# config-bank6.net
KiCad netlist of a schematic drawn in Altium Designer
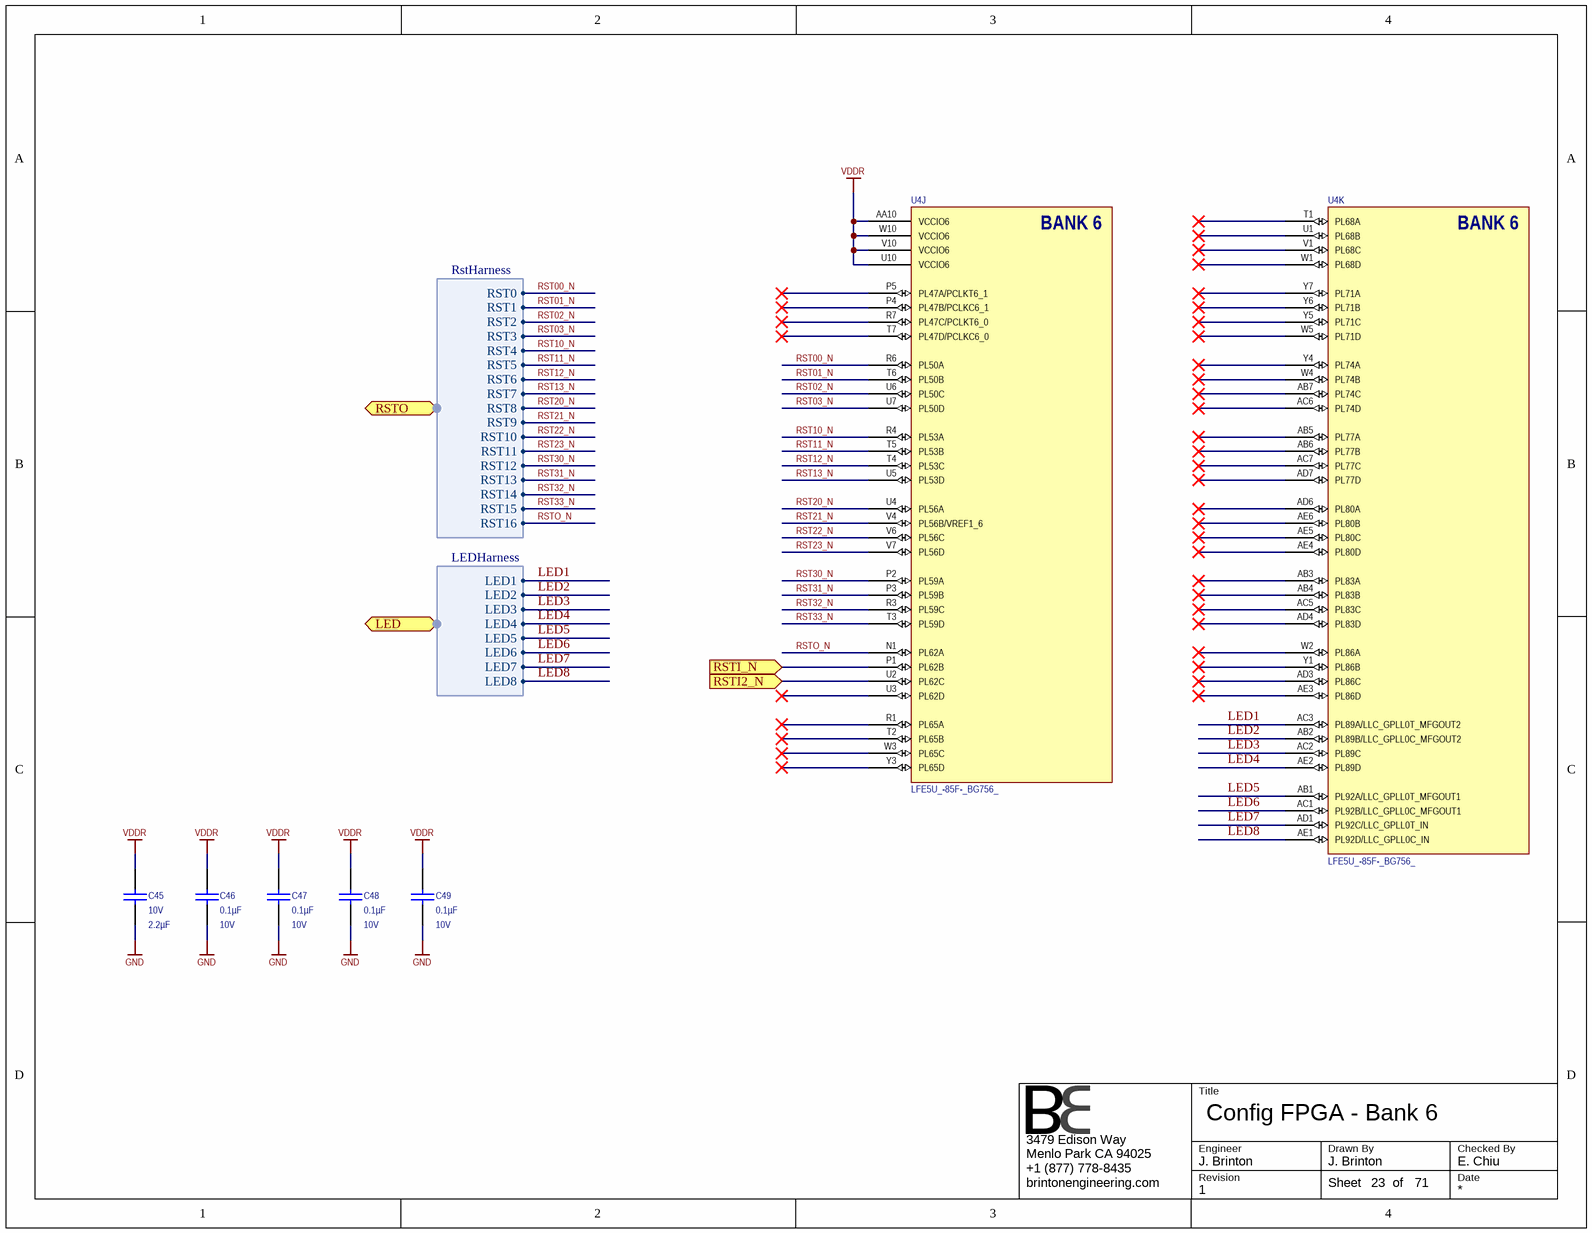
[diagram p0: config-bank6.SchDoc]

(export (version "E")
  (design (tool "Eeschema 10.0.6"))
  (components
    (comp (ref "C45")
      (value "GRM188R71A225KE15D")
      (footprint "CAPC1608X90N")
      (description "CAP CER 2.2UF 10V 10% X7R 0603")
      (fields
        (field (name "MANUFACTURER") "Murata Electronics North America")
        (field (name "TOLERANCE") "±10%")
        (field (name "VOLTAGE - RATED") "10V")
        (field (name "CAPACITANCE") "2.2µF")
      )
      (libsource (lib "murata") (part "GRM188R71A225KE15D"))
    )
    (comp (ref "C46")
      (value "GRM155R71A104KA01J")
      (footprint "CAPC1005X56N")
      (description "CAP CER 0.1UF 10V 10% X7R 0402")
      (fields
        (field (name "MANUFACTURER") "Murata Electronics North America")
        (field (name "TOLERANCE") "±10%")
        (field (name "CAPACITANCE") "0.1µF")
        (field (name "VOLTAGE - RATED") "10V")
      )
      (libsource (lib "murata") (part "GRM155R71A104KA01J"))
    )
    (comp (ref "C47")
      (value "GRM155R71A104KA01J")
      (footprint "CAPC1005X56N")
      (description "CAP CER 0.1UF 10V 10% X7R 0402")
      (fields
        (field (name "MANUFACTURER") "Murata Electronics North America")
        (field (name "TOLERANCE") "±10%")
        (field (name "CAPACITANCE") "0.1µF")
        (field (name "VOLTAGE - RATED") "10V")
      )
      (libsource (lib "murata") (part "GRM155R71A104KA01J"))
    )
    (comp (ref "C48")
      (value "GRM155R71A104KA01J")
      (footprint "CAPC1005X56N")
      (description "CAP CER 0.1UF 10V 10% X7R 0402")
      (fields
        (field (name "MANUFACTURER") "Murata Electronics North America")
        (field (name "TOLERANCE") "±10%")
        (field (name "CAPACITANCE") "0.1µF")
        (field (name "VOLTAGE - RATED") "10V")
      )
      (libsource (lib "murata") (part "GRM155R71A104KA01J"))
    )
    (comp (ref "C49")
      (value "GRM155R71A104KA01J")
      (footprint "CAPC1005X56N")
      (description "CAP CER 0.1UF 10V 10% X7R 0402")
      (fields
        (field (name "MANUFACTURER") "Murata Electronics North America")
        (field (name "TOLERANCE") "±10%")
        (field (name "CAPACITANCE") "0.1µF")
        (field (name "VOLTAGE - RATED") "10V")
      )
      (libsource (lib "murata") (part "GRM155R71A104KA01J"))
    )
    (comp (ref "U4")
      (value "LFE5U_-85F-_BG756_")
      (footprint "lattice:caBGA756")
      (description "ECP5 FPGA, 85k LUT, 756-caBGA")
      (fields (field (name "MANUFACTURER") "Lattice Semiconductor"))
      (libsource (lib "lattice") (part "LFE5U_-85F-_BG756_"))
    )
  )
  (nets
    (net (code "3") (name "/LED1") (class "Default")
      (node (ref "U4") (pin "AC3") (pinfunction "PL89A/LLC_GPLL0T_MFGOUT2_AC3") (pintype "bidirectional"))
    )
    (net (code "4") (name "/LED2") (class "Default")
      (node (ref "U4") (pin "AB2") (pinfunction "PL89B/LLC_GPLL0C_MFGOUT2_AB2") (pintype "bidirectional"))
    )
    (net (code "5") (name "/LED3") (class "Default")
      (node (ref "U4") (pin "AC2") (pinfunction "PL89C_AC2") (pintype "bidirectional"))
    )
    (net (code "6") (name "/LED4") (class "Default")
      (node (ref "U4") (pin "AE2") (pinfunction "PL89D_AE2") (pintype "bidirectional"))
    )
    (net (code "7") (name "/LED5") (class "Default")
      (node (ref "U4") (pin "AB1") (pinfunction "PL92A/LLC_GPLL0T_MFGOUT1_AB1") (pintype "bidirectional"))
    )
    (net (code "8") (name "/LED6") (class "Default")
      (node (ref "U4") (pin "AC1") (pinfunction "PL92B/LLC_GPLL0C_MFGOUT1_AC1") (pintype "bidirectional"))
    )
    (net (code "9") (name "/LED7") (class "Default")
      (node (ref "U4") (pin "AD1") (pinfunction "PL92C/LLC_GPLL0T_IN_AD1") (pintype "bidirectional"))
    )
    (net (code "10") (name "/LED8") (class "Default")
      (node (ref "U4") (pin "AE1") (pinfunction "PL92D/LLC_GPLL0C_IN_AE1") (pintype "bidirectional"))
    )
    (net (code "11") (name "/RST00_N") (class "Default")
      (node (ref "U4") (pin "R6") (pinfunction "PL50A_R6") (pintype "bidirectional"))
    )
    (net (code "12") (name "/RST01_N") (class "Default")
      (node (ref "U4") (pin "T6") (pinfunction "PL50B_T6") (pintype "bidirectional"))
    )
    (net (code "13") (name "/RST02_N") (class "Default")
      (node (ref "U4") (pin "U6") (pinfunction "PL50C_U6") (pintype "bidirectional"))
    )
    (net (code "14") (name "/RST03_N") (class "Default")
      (node (ref "U4") (pin "U7") (pinfunction "PL50D_U7") (pintype "bidirectional"))
    )
    (net (code "15") (name "/RST10_N") (class "Default")
      (node (ref "U4") (pin "R4") (pinfunction "PL53A_R4") (pintype "bidirectional"))
    )
    (net (code "16") (name "/RST11_N") (class "Default")
      (node (ref "U4") (pin "T5") (pinfunction "PL53B_T5") (pintype "bidirectional"))
    )
    (net (code "17") (name "/RST12_N") (class "Default")
      (node (ref "U4") (pin "T4") (pinfunction "PL53C_T4") (pintype "bidirectional"))
    )
    (net (code "18") (name "/RST13_N") (class "Default")
      (node (ref "U4") (pin "U5") (pinfunction "PL53D_U5") (pintype "bidirectional"))
    )
    (net (code "19") (name "/RST20_N") (class "Default")
      (node (ref "U4") (pin "U4") (pinfunction "PL56A_U4") (pintype "bidirectional"))
    )
    (net (code "20") (name "/RST21_N") (class "Default")
      (node (ref "U4") (pin "V4") (pinfunction "PL56B/VREF1_6_V4") (pintype "bidirectional"))
    )
    (net (code "21") (name "/RST22_N") (class "Default")
      (node (ref "U4") (pin "V6") (pinfunction "PL56C_V6") (pintype "bidirectional"))
    )
    (net (code "22") (name "/RST23_N") (class "Default")
      (node (ref "U4") (pin "V7") (pinfunction "PL56D_V7") (pintype "bidirectional"))
    )
    (net (code "23") (name "/RST30_N") (class "Default")
      (node (ref "U4") (pin "P2") (pinfunction "PL59A_P2") (pintype "bidirectional"))
    )
    (net (code "24") (name "/RST31_N") (class "Default")
      (node (ref "U4") (pin "P3") (pinfunction "PL59B_P3") (pintype "bidirectional"))
    )
    (net (code "25") (name "/RST32_N") (class "Default")
      (node (ref "U4") (pin "R3") (pinfunction "PL59C_R3") (pintype "bidirectional"))
    )
    (net (code "26") (name "/RST33_N") (class "Default")
      (node (ref "U4") (pin "T3") (pinfunction "PL59D_T3") (pintype "bidirectional"))
    )
    (net (code "27") (name "/RSTI2_N") (class "Default")
      (node (ref "U4") (pin "U2") (pinfunction "PL62C_U2") (pintype "bidirectional"))
    )
    (net (code "28") (name "/RSTI_N") (class "Default")
      (node (ref "U4") (pin "P1") (pinfunction "PL62B_P1") (pintype "bidirectional"))
    )
    (net (code "29") (name "/RSTO_N") (class "Default")
      (node (ref "U4") (pin "N1") (pinfunction "PL62A_N1") (pintype "bidirectional"))
    )
    (net (code "32") (name "GND") (class "Default")
      (node (ref "C45") (pin "1") (pinfunction "1_1") (pintype "passive"))
      (node (ref "C46") (pin "1") (pinfunction "1_1") (pintype "passive"))
      (node (ref "C47") (pin "1") (pinfunction "1_1") (pintype "passive"))
      (node (ref "C48") (pin "1") (pinfunction "1_1") (pintype "passive"))
      (node (ref "C49") (pin "1") (pinfunction "1_1") (pintype "passive"))
    )
    (net (code "33") (name "VDDR") (class "Default")
      (node (ref "C45") (pin "2") (pinfunction "2_2") (pintype "passive"))
      (node (ref "C46") (pin "2") (pinfunction "2_2") (pintype "passive"))
      (node (ref "C47") (pin "2") (pinfunction "2_2") (pintype "passive"))
      (node (ref "C48") (pin "2") (pinfunction "2_2") (pintype "passive"))
      (node (ref "C49") (pin "2") (pinfunction "2_2") (pintype "passive"))
      (node (ref "U4") (pin "AA10") (pinfunction "VCCIO6_AA10") (pintype "power_in"))
      (node (ref "U4") (pin "U10") (pinfunction "VCCIO6_U10") (pintype "power_in"))
      (node (ref "U4") (pin "V10") (pinfunction "VCCIO6_V10") (pintype "power_in"))
      (node (ref "U4") (pin "W10") (pinfunction "VCCIO6_W10") (pintype "power_in"))
    )
    (net (code "34") (name "unconnected-(U4J-PL47A{slash}PCLKT6_1-PadP5)") (class "Default")
      (node (ref "U4") (pin "P5") (pinfunction "PL47A/PCLKT6_1_P5") (pintype "bidirectional+no_connect"))
    )
    (net (code "35") (name "unconnected-(U4J-PL47B{slash}PCLKC6_1-PadP4)") (class "Default")
      (node (ref "U4") (pin "P4") (pinfunction "PL47B/PCLKC6_1_P4") (pintype "bidirectional+no_connect"))
    )
    (net (code "36") (name "unconnected-(U4J-PL47C{slash}PCLKT6_0-PadR7)") (class "Default")
      (node (ref "U4") (pin "R7") (pinfunction "PL47C/PCLKT6_0_R7") (pintype "bidirectional+no_connect"))
    )
    (net (code "37") (name "unconnected-(U4J-PL47D{slash}PCLKC6_0-PadT7)") (class "Default")
      (node (ref "U4") (pin "T7") (pinfunction "PL47D/PCLKC6_0_T7") (pintype "bidirectional+no_connect"))
    )
    (net (code "38") (name "unconnected-(U4J-PL62D-PadU3)") (class "Default")
      (node (ref "U4") (pin "U3") (pinfunction "PL62D_U3") (pintype "bidirectional+no_connect"))
    )
    (net (code "39") (name "unconnected-(U4J-PL65A-PadR1)") (class "Default")
      (node (ref "U4") (pin "R1") (pinfunction "PL65A_R1") (pintype "bidirectional+no_connect"))
    )
    (net (code "40") (name "unconnected-(U4J-PL65B-PadT2)") (class "Default")
      (node (ref "U4") (pin "T2") (pinfunction "PL65B_T2") (pintype "bidirectional+no_connect"))
    )
    (net (code "41") (name "unconnected-(U4J-PL65C-PadW3)") (class "Default")
      (node (ref "U4") (pin "W3") (pinfunction "PL65C_W3") (pintype "bidirectional+no_connect"))
    )
    (net (code "42") (name "unconnected-(U4J-PL65D-PadY3)") (class "Default")
      (node (ref "U4") (pin "Y3") (pinfunction "PL65D_Y3") (pintype "bidirectional+no_connect"))
    )
    (net (code "43") (name "unconnected-(U4K-PL68A-PadT1)") (class "Default")
      (node (ref "U4") (pin "T1") (pinfunction "PL68A_T1") (pintype "bidirectional+no_connect"))
    )
    (net (code "44") (name "unconnected-(U4K-PL68B-PadU1)") (class "Default")
      (node (ref "U4") (pin "U1") (pinfunction "PL68B_U1") (pintype "bidirectional+no_connect"))
    )
    (net (code "45") (name "unconnected-(U4K-PL68C-PadV1)") (class "Default")
      (node (ref "U4") (pin "V1") (pinfunction "PL68C_V1") (pintype "bidirectional+no_connect"))
    )
    (net (code "46") (name "unconnected-(U4K-PL68D-PadW1)") (class "Default")
      (node (ref "U4") (pin "W1") (pinfunction "PL68D_W1") (pintype "bidirectional+no_connect"))
    )
    (net (code "47") (name "unconnected-(U4K-PL71A-PadY7)") (class "Default")
      (node (ref "U4") (pin "Y7") (pinfunction "PL71A_Y7") (pintype "bidirectional+no_connect"))
    )
    (net (code "48") (name "unconnected-(U4K-PL71B-PadY6)") (class "Default")
      (node (ref "U4") (pin "Y6") (pinfunction "PL71B_Y6") (pintype "bidirectional+no_connect"))
    )
    (net (code "49") (name "unconnected-(U4K-PL71C-PadY5)") (class "Default")
      (node (ref "U4") (pin "Y5") (pinfunction "PL71C_Y5") (pintype "bidirectional+no_connect"))
    )
    (net (code "50") (name "unconnected-(U4K-PL71D-PadW5)") (class "Default")
      (node (ref "U4") (pin "W5") (pinfunction "PL71D_W5") (pintype "bidirectional+no_connect"))
    )
    (net (code "51") (name "unconnected-(U4K-PL74A-PadY4)") (class "Default")
      (node (ref "U4") (pin "Y4") (pinfunction "PL74A_Y4") (pintype "bidirectional+no_connect"))
    )
    (net (code "52") (name "unconnected-(U4K-PL74B-PadW4)") (class "Default")
      (node (ref "U4") (pin "W4") (pinfunction "PL74B_W4") (pintype "bidirectional+no_connect"))
    )
    (net (code "53") (name "unconnected-(U4K-PL74C-PadAB7)") (class "Default")
      (node (ref "U4") (pin "AB7") (pinfunction "PL74C_AB7") (pintype "bidirectional+no_connect"))
    )
    (net (code "54") (name "unconnected-(U4K-PL74D-PadAC6)") (class "Default")
      (node (ref "U4") (pin "AC6") (pinfunction "PL74D_AC6") (pintype "bidirectional+no_connect"))
    )
    (net (code "55") (name "unconnected-(U4K-PL77A-PadAB5)") (class "Default")
      (node (ref "U4") (pin "AB5") (pinfunction "PL77A_AB5") (pintype "bidirectional+no_connect"))
    )
    (net (code "56") (name "unconnected-(U4K-PL77B-PadAB6)") (class "Default")
      (node (ref "U4") (pin "AB6") (pinfunction "PL77B_AB6") (pintype "bidirectional+no_connect"))
    )
    (net (code "57") (name "unconnected-(U4K-PL77C-PadAC7)") (class "Default")
      (node (ref "U4") (pin "AC7") (pinfunction "PL77C_AC7") (pintype "bidirectional+no_connect"))
    )
    (net (code "58") (name "unconnected-(U4K-PL77D-PadAD7)") (class "Default")
      (node (ref "U4") (pin "AD7") (pinfunction "PL77D_AD7") (pintype "bidirectional+no_connect"))
    )
    (net (code "59") (name "unconnected-(U4K-PL80A-PadAD6)") (class "Default")
      (node (ref "U4") (pin "AD6") (pinfunction "PL80A_AD6") (pintype "bidirectional+no_connect"))
    )
    (net (code "60") (name "unconnected-(U4K-PL80B-PadAE6)") (class "Default")
      (node (ref "U4") (pin "AE6") (pinfunction "PL80B_AE6") (pintype "bidirectional+no_connect"))
    )
    (net (code "61") (name "unconnected-(U4K-PL80C-PadAE5)") (class "Default")
      (node (ref "U4") (pin "AE5") (pinfunction "PL80C_AE5") (pintype "bidirectional+no_connect"))
    )
    (net (code "62") (name "unconnected-(U4K-PL80D-PadAE4)") (class "Default")
      (node (ref "U4") (pin "AE4") (pinfunction "PL80D_AE4") (pintype "bidirectional+no_connect"))
    )
    (net (code "63") (name "unconnected-(U4K-PL83A-PadAB3)") (class "Default")
      (node (ref "U4") (pin "AB3") (pinfunction "PL83A_AB3") (pintype "bidirectional+no_connect"))
    )
    (net (code "64") (name "unconnected-(U4K-PL83B-PadAB4)") (class "Default")
      (node (ref "U4") (pin "AB4") (pinfunction "PL83B_AB4") (pintype "bidirectional+no_connect"))
    )
    (net (code "65") (name "unconnected-(U4K-PL83C-PadAC5)") (class "Default")
      (node (ref "U4") (pin "AC5") (pinfunction "PL83C_AC5") (pintype "bidirectional+no_connect"))
    )
    (net (code "66") (name "unconnected-(U4K-PL83D-PadAD4)") (class "Default")
      (node (ref "U4") (pin "AD4") (pinfunction "PL83D_AD4") (pintype "bidirectional+no_connect"))
    )
    (net (code "67") (name "unconnected-(U4K-PL86A-PadW2)") (class "Default")
      (node (ref "U4") (pin "W2") (pinfunction "PL86A_W2") (pintype "bidirectional+no_connect"))
    )
    (net (code "68") (name "unconnected-(U4K-PL86B-PadY1)") (class "Default")
      (node (ref "U4") (pin "Y1") (pinfunction "PL86B_Y1") (pintype "bidirectional+no_connect"))
    )
    (net (code "69") (name "unconnected-(U4K-PL86C-PadAD3)") (class "Default")
      (node (ref "U4") (pin "AD3") (pinfunction "PL86C_AD3") (pintype "bidirectional+no_connect"))
    )
    (net (code "70") (name "unconnected-(U4K-PL86D-PadAE3)") (class "Default")
      (node (ref "U4") (pin "AE3") (pinfunction "PL86D_AE3") (pintype "bidirectional+no_connect"))
    )
  )
)
